# Analog_HC_Overcurrent_Redundancy.net
KiCad netlist of a schematic drawn in Altium Designer
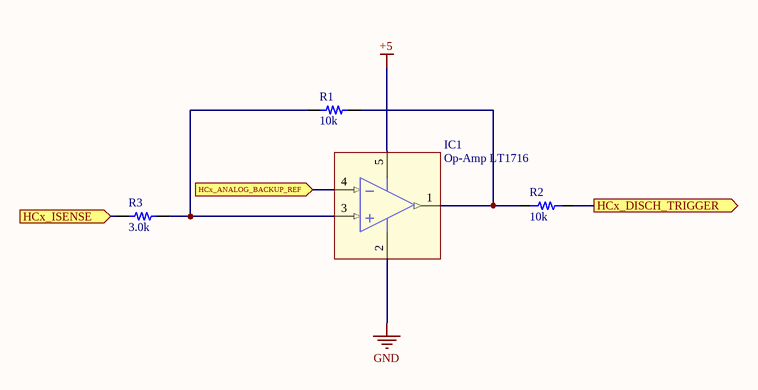
[diagram p0: Analog_HC_Overcurrent_Redundancy.SchDoc]

(export (version "E")
  (design (tool "Eeschema 10.0.6"))
  (components
    (comp (ref "IC1")
      (value "Op-Amp LT1716")
      (footprint "SOT23-5")
      (fields (field (name "MFRPARTNO") "LT1716IS5#PBF"))
      (libsource (lib "Altium-Lib") (part "Op-Amp LT1716"))
    )
    (comp (ref "R1")
      (value "10k")
      (footprint "RES 0603/1608")
      (fields
        (field (name "TOLERANCE") "1%")
        (field (name "POWER") "1/10W")
        (field (name "Comment") "Resistor 10k 0603 1/10W 1%")
        (field (name "CREATED_BY") "Nick Mah")
      )
      (libsource (lib "Altium-Lib") (part "Resistor"))
    )
    (comp (ref "R2")
      (value "10k")
      (footprint "RES 0805/2012")
      (fields
        (field (name "TOLERANCE") "1%")
        (field (name "POWER") "1/10W")
        (field (name "Comment") "Resistor 10k 0805 1/10W 1%")
        (field (name "CREATED_BY") "Nick Mah")
      )
      (libsource (lib "") (part "Resistor_1"))
    )
    (comp (ref "R3")
      (value "3.0k")
      (footprint "RES 0603/1608")
      (fields
        (field (name "TOLERANCE") "1%")
        (field (name "POWER") "1/10W")
        (field (name "Comment") "Resistor 3.0k 0603 1/10W 1%")
        (field (name "CREATED_BY") "Nick Mah")
      )
      (libsource (lib "Altium-Lib") (part "Resistor"))
    )
  )
  (nets
    (net (code "1") (name "+5") (class "Default")
      (node (ref "IC1") (pin "5") (pinfunction "V+_5") (pintype "power_in"))
    )
    (net (code "2") (name "/HCx_ANALOG_BACKUP_REF") (class "Default")
      (node (ref "IC1") (pin "4") (pinfunction "IN-_4") (pintype "input"))
    )
    (net (code "3") (name "/HCx_DISCH_TRIGGER") (class "Default")
      (node (ref "R2") (pin "2") (pinfunction "2_2") (pintype "passive"))
    )
    (net (code "4") (name "/HCx_ISENSE") (class "Default")
      (node (ref "R3") (pin "1") (pinfunction "1_1") (pintype "passive"))
    )
    (net (code "5") (name "GND") (class "Default")
      (node (ref "IC1") (pin "2") (pinfunction "V-_2") (pintype "power_in"))
    )
    (net (code "6") (name "Net-(IC1-IN+)") (class "Default")
      (node (ref "IC1") (pin "3") (pinfunction "IN+_3") (pintype "input"))
      (node (ref "R1") (pin "1") (pinfunction "1_1") (pintype "passive"))
      (node (ref "R3") (pin "2") (pinfunction "2_2") (pintype "passive"))
    )
    (net (code "7") (name "Net-(IC1-OUT)") (class "Default")
      (node (ref "IC1") (pin "1") (pinfunction "OUT_1") (pintype "output"))
      (node (ref "R1") (pin "2") (pinfunction "2_2") (pintype "passive"))
      (node (ref "R2") (pin "1") (pinfunction "1_1") (pintype "passive"))
    )
  )
)
